# 6coils-1-discrete.net
KiCad netlist of a schematic drawn in EasyEDA
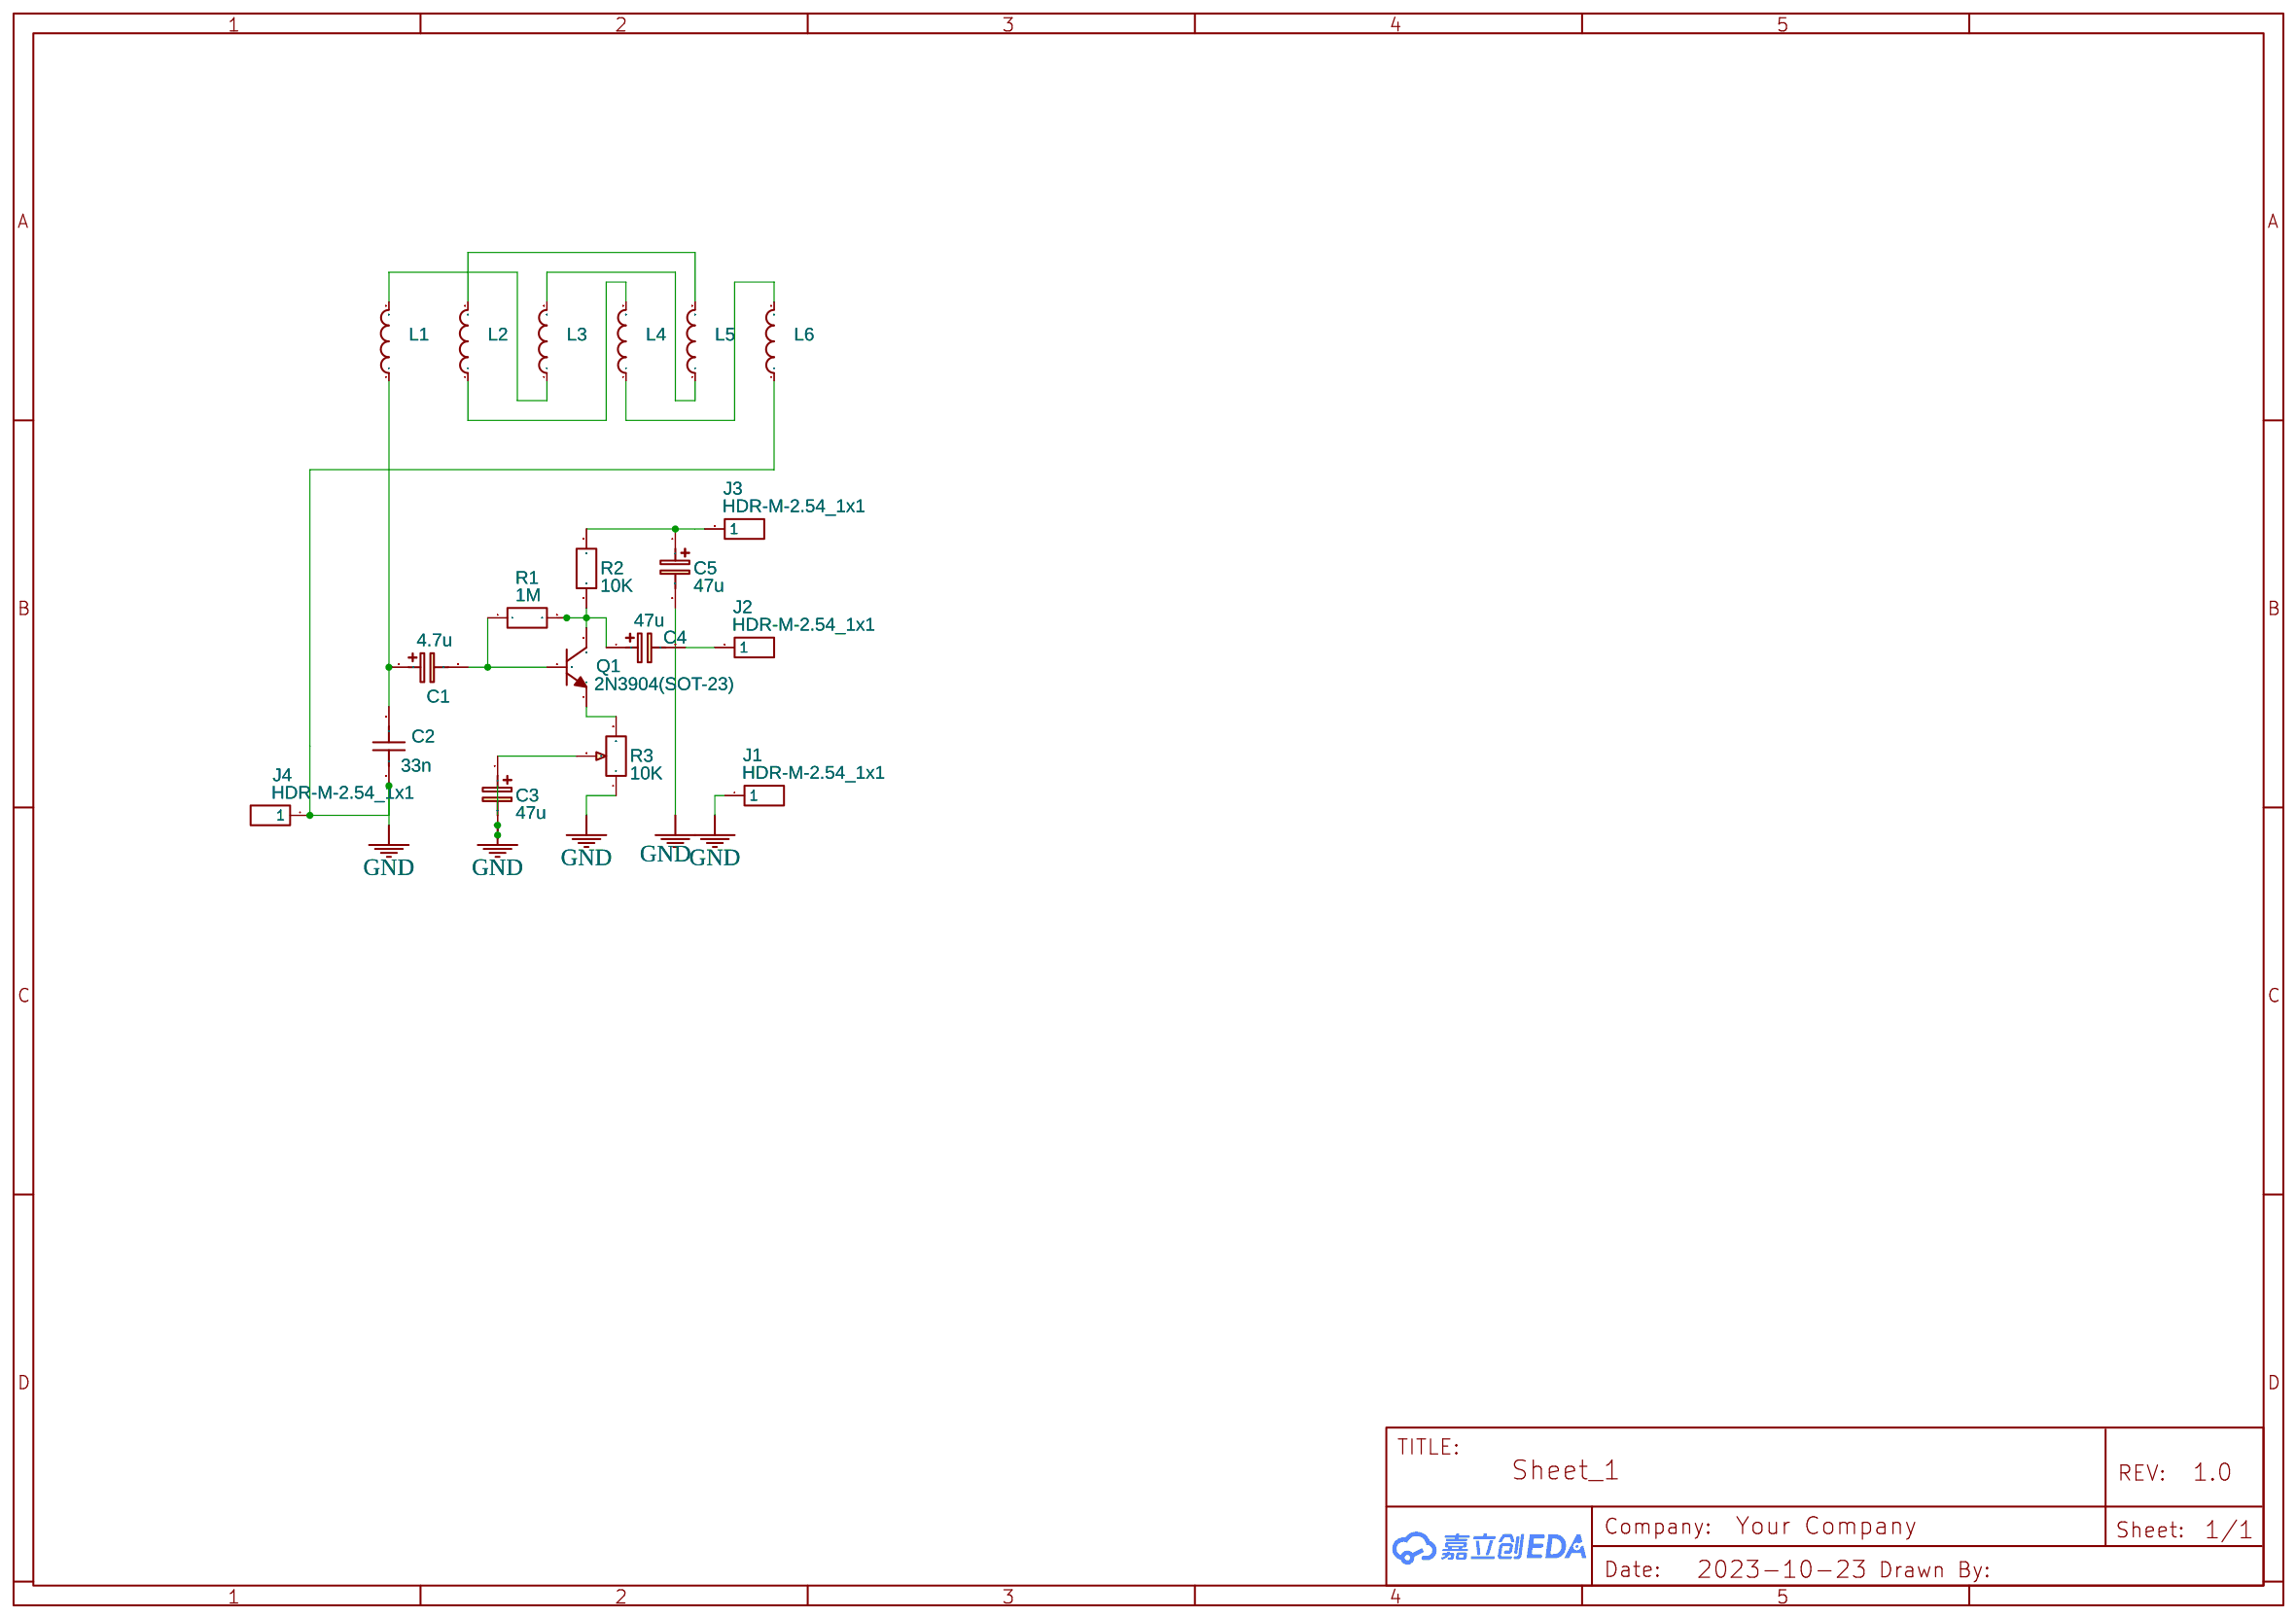
[diagram p0: schematic sheet]

(export (version "E")
  (design (tool "Eeschema 10.0.6"))
  (components
    (comp (ref "C1") (value "4.7u") (libsource (lib "") (part "C_Tan_SMD_A_EU_1")))
    (comp (ref "C2") (value "33n") (libsource (lib "") (part "C_0603_US")))
    (comp (ref "C3") (value "47u") (libsource (lib "") (part "C_Tan_SMD_A_EU_3")))
    (comp (ref "C4") (value "47u") (libsource (lib "") (part "C_Tan_SMD_A_EU")))
    (comp (ref "C5") (value "47u") (libsource (lib "") (part "C_Tan_SMD_A_EU_2")))
    (comp (ref "J1")
      (value "HDR-M-2.54_1x1")
      (fields (field (name "BOM_Supplier Part") "C81276"))
      (libsource (lib "") (part "HDR-M-2.54_1x1"))
    )
    (comp (ref "J2")
      (value "HDR-M-2.54_1x1")
      (fields (field (name "BOM_Supplier Part") "C81276"))
      (libsource (lib "") (part "HDR-M-2.54_1x1"))
    )
    (comp (ref "J3")
      (value "HDR-M-2.54_1x1")
      (fields (field (name "BOM_Supplier Part") "C81276"))
      (libsource (lib "") (part "HDR-M-2.54_1x1"))
    )
    (comp (ref "J4")
      (value "HDR-M-2.54_1x1")
      (fields (field (name "BOM_Supplier Part") "C81276"))
      (libsource (lib "") (part "HDR-M-2.54_1x1_1"))
    )
    (comp (ref "L1")
      (value "INDUCTOR_SMD:L_COILCRAFT_XXL4040")
      (fields (field (name "Manufacturer Part") "Inductor_SMD:L_Coilcraft_XxL4040"))
      (libsource (lib "") (part "INDUCTOR_SMD{colon}L_COILCRAFT_XXL4040_1"))
    )
    (comp (ref "L2")
      (value "INDUCTOR_SMD:L_COILCRAFT_XXL4040")
      (fields (field (name "Manufacturer Part") "Inductor_SMD:L_Coilcraft_XxL4040"))
      (libsource (lib "") (part "INDUCTOR_SMD{colon}L_COILCRAFT_XXL4040_1"))
    )
    (comp (ref "L3")
      (value "INDUCTOR_SMD:L_COILCRAFT_XXL4040")
      (fields (field (name "Manufacturer Part") "Inductor_SMD:L_Coilcraft_XxL4040"))
      (libsource (lib "") (part "INDUCTOR_SMD{colon}L_COILCRAFT_XXL4040"))
    )
    (comp (ref "L4")
      (value "INDUCTOR_SMD:L_COILCRAFT_XXL4040")
      (fields (field (name "Manufacturer Part") "Inductor_SMD:L_Coilcraft_XxL4040"))
      (libsource (lib "") (part "INDUCTOR_SMD{colon}L_COILCRAFT_XXL4040"))
    )
    (comp (ref "L5")
      (value "INDUCTOR_SMD:L_COILCRAFT_XXL4040")
      (fields (field (name "Manufacturer Part") "Inductor_SMD:L_Coilcraft_XxL4040"))
      (libsource (lib "") (part "INDUCTOR_SMD{colon}L_COILCRAFT_XXL4040"))
    )
    (comp (ref "L6")
      (value "INDUCTOR_SMD:L_COILCRAFT_XXL4040")
      (fields (field (name "Manufacturer Part") "Inductor_SMD:L_Coilcraft_XxL4040"))
      (libsource (lib "") (part "INDUCTOR_SMD{colon}L_COILCRAFT_XXL4040"))
    )
    (comp (ref "Q1")
      (value "2N3904(SOT-23)")
      (fields
        (field (name "BOM_Manufacturer Part") "2n3904S-RTK/PS")
        (field (name "BOM_Supplier Part") "C18536")
      )
      (libsource (lib "") (part "2N3904(SOT-23)"))
    )
    (comp (ref "R1") (value "1M") (libsource (lib "") (part "R_0603_EU")))
    (comp (ref "R2") (value "10K") (libsource (lib "") (part "R_0603_EU_1")))
    (comp (ref "R3")
      (value "10K")
      (fields (field (name "Manufacturer Part") "RM063-103 10K") (field (name "Manufacturer") "JML"))
      (libsource (lib "") (part "RM063-103 10K"))
    )
  )
  (nets
    (net (code "1") (name "GND") (class "Default")
      (node (ref "C2") (pin "1") (pinfunction "1_1") (pintype "unspecified"))
      (node (ref "C3") (pin "2") (pinfunction "2_2") (pintype "unspecified"))
      (node (ref "C5") (pin "2") (pinfunction "2_2") (pintype "unspecified"))
      (node (ref "J1") (pin "1") (pinfunction "1_1") (pintype "input"))
      (node (ref "J4") (pin "1") (pinfunction "1_1") (pintype "input"))
      (node (ref "L6") (pin "1") (pinfunction "1_1") (pintype "unspecified"))
      (node (ref "R3") (pin "1") (pinfunction "1_1") (pintype "input"))
    )
    (net (code "2") (name "Net-(C1-Pad1)") (class "Default")
      (node (ref "C1") (pin "1") (pinfunction "1_1") (pintype "unspecified"))
      (node (ref "C2") (pin "2") (pinfunction "2_2") (pintype "unspecified"))
      (node (ref "L1") (pin "1") (pinfunction "1_1") (pintype "unspecified"))
    )
    (net (code "3") (name "Net-(C3-Pad1)") (class "Default")
      (node (ref "C3") (pin "1") (pinfunction "1_1") (pintype "unspecified"))
      (node (ref "R3") (pin "2") (pinfunction "2_2") (pintype "input"))
    )
    (net (code "4") (name "Net-(C4-Pad2)") (class "Default")
      (node (ref "C4") (pin "2") (pinfunction "2_2") (pintype "unspecified"))
      (node (ref "J2") (pin "1") (pinfunction "1_1") (pintype "input"))
    )
    (net (code "5") (name "Net-(C5-Pad1)") (class "Default")
      (node (ref "C5") (pin "1") (pinfunction "1_1") (pintype "unspecified"))
      (node (ref "J3") (pin "1") (pinfunction "1_1") (pintype "input"))
      (node (ref "R2") (pin "2") (pinfunction "2_2") (pintype "unspecified"))
    )
    (net (code "6") (name "Net-(L1-Pad2)") (class "Default")
      (node (ref "L1") (pin "2") (pinfunction "2_2") (pintype "unspecified"))
      (node (ref "L3") (pin "1") (pinfunction "1_1") (pintype "unspecified"))
    )
    (net (code "7") (name "Net-(L2-Pad1)") (class "Default")
      (node (ref "L2") (pin "1") (pinfunction "1_1") (pintype "unspecified"))
      (node (ref "L4") (pin "2") (pinfunction "2_2") (pintype "unspecified"))
    )
    (net (code "8") (name "Net-(L2-Pad2)") (class "Default")
      (node (ref "L2") (pin "2") (pinfunction "2_2") (pintype "unspecified"))
      (node (ref "L5") (pin "2") (pinfunction "2_2") (pintype "unspecified"))
    )
    (net (code "9") (name "Net-(L3-Pad2)") (class "Default")
      (node (ref "L3") (pin "2") (pinfunction "2_2") (pintype "unspecified"))
      (node (ref "L5") (pin "1") (pinfunction "1_1") (pintype "unspecified"))
    )
    (net (code "10") (name "Net-(L4-Pad1)") (class "Default")
      (node (ref "L4") (pin "1") (pinfunction "1_1") (pintype "unspecified"))
      (node (ref "L6") (pin "2") (pinfunction "2_2") (pintype "unspecified"))
    )
    (net (code "11") (name "Net-(Q1-B)") (class "Default")
      (node (ref "C1") (pin "2") (pinfunction "2_2") (pintype "unspecified"))
      (node (ref "Q1") (pin "2") (pinfunction "B_2") (pintype "input"))
      (node (ref "R1") (pin "1") (pinfunction "1_1") (pintype "unspecified"))
    )
    (net (code "12") (name "Net-(Q1-C)") (class "Default")
      (node (ref "C4") (pin "1") (pinfunction "1_1") (pintype "unspecified"))
      (node (ref "Q1") (pin "3") (pinfunction "C_3") (pintype "input"))
      (node (ref "R1") (pin "2") (pinfunction "2_2") (pintype "unspecified"))
      (node (ref "R2") (pin "1") (pinfunction "1_1") (pintype "unspecified"))
    )
    (net (code "13") (name "Net-(Q1-E)") (class "Default")
      (node (ref "Q1") (pin "1") (pinfunction "E_1") (pintype "input"))
      (node (ref "R3") (pin "3") (pinfunction "3_3") (pintype "input"))
    )
  )
)
